# NG2094_IR_Flood.net
KiCad netlist of a schematic drawn in Altium Designer
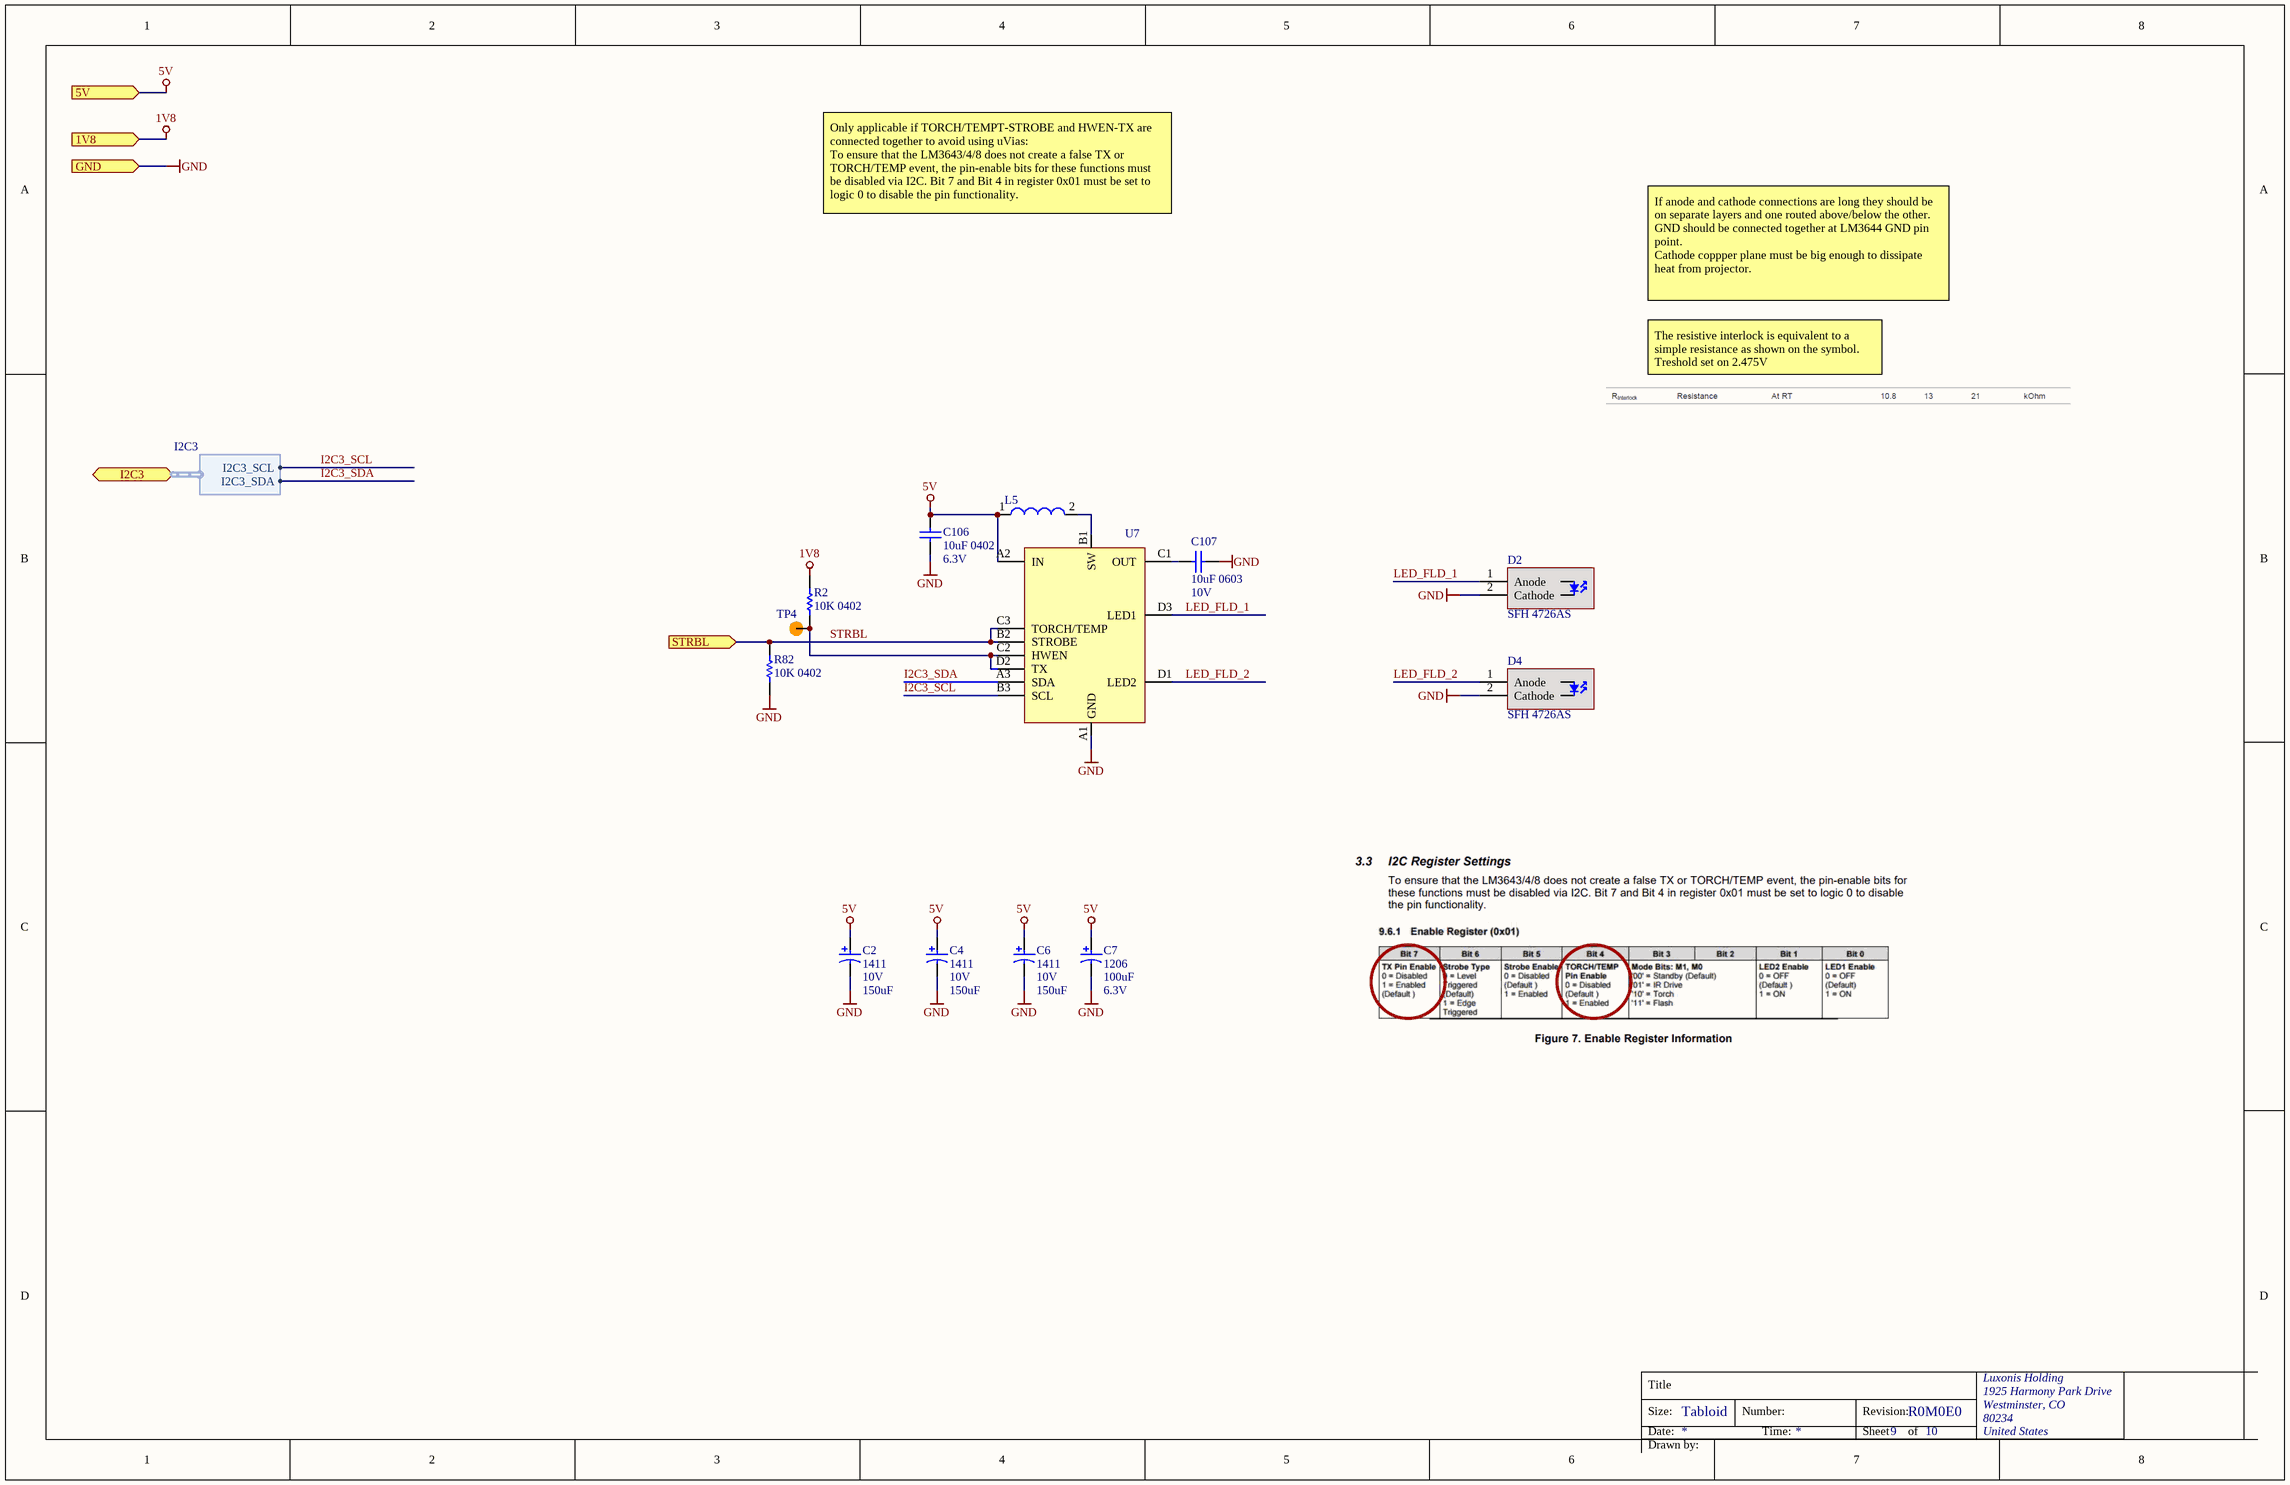
[diagram p0: NG2094_IR_Flood.SchDoc]

(export (version "E")
  (design (tool "Eeschema 10.0.6"))
  (components
    (comp (ref "C2")
      (value "150uF 1206 10V tantal")
      (footprint "RESTL1210(3225)_N")
      (fields
        (field (name "SIZE CODE") "1411")
        (field (name "RATED DC VOLTAGE (URDC)") "10V")
        (field (name "CAPACITANCE") "150uF")
      )
      (libsource (lib "NG2094") (part "TLJB157M010R0500"))
    )
    (comp (ref "C4")
      (value "150uF 1206 10V tantal")
      (footprint "RESTL1210(3225)_N")
      (fields
        (field (name "SIZE CODE") "1411")
        (field (name "RATED DC VOLTAGE (URDC)") "10V")
        (field (name "CAPACITANCE") "150uF")
      )
      (libsource (lib "NG2094") (part "TLJB157M010R0500"))
    )
    (comp (ref "C6")
      (value "150uF 1206 10V tantal")
      (footprint "RESTL1210(3225)_N")
      (fields
        (field (name "SIZE CODE") "1411")
        (field (name "RATED DC VOLTAGE (URDC)") "10V")
        (field (name "CAPACITANCE") "150uF")
      )
      (libsource (lib "NG2094") (part "TLJB157M010R0500"))
    )
    (comp (ref "C7")
      (value "100uF 1206 6V3 tantal")
      (footprint "RESTL1206(3216)_L")
      (fields
        (field (name "SIZE CODE") "1206")
        (field (name "CAPACITANCE") "100uF")
        (field (name "RATED DC VOLTAGE (URDC)") "6.3V")
      )
      (libsource (lib "NG2094") (part "TLJA107M006R0500"))
    )
    (comp (ref "C106")
      (value "10uF 0402")
      (footprint "CAP_Altium_Vault_Generic:CAPC0402(1005)70_L")
      (description "CAP CER 10UF 6.3V X5R 0402 20%")
      (fields (field (name "TOLERANCE") "20%") (field (name "VOLTAGE RATING") "6.3V"))
      (libsource (lib "LuxonisMaster") (part "GRM155R60J106ME15D"))
    )
    (comp (ref "C107")
      (value "10uF 0603")
      (footprint "CAP_Altium_Vault_Generic:CAPC0603(1608)100_L")
      (description "CAP CER 10UF 10V X5R 0603 20%")
      (fields (field (name "TOLERANCE") "20%") (field (name "VOLTAGE RATING") "10V"))
      (libsource (lib "LuxonisMaster") (part "GRM188R61A106ME69D"))
    )
    (comp (ref "D2")
      (value "SFH 4726AS")
      (footprint "SFH 4726AS")
      (description "OSLON Black Series (940 nm) - 150°")
      (libsource (lib "NG2094") (part "SFH 4726AS"))
    )
    (comp (ref "D4")
      (value "SFH 4726AS")
      (footprint "SFH 4726AS")
      (description "OSLON Black Series (940 nm) - 150°")
      (libsource (lib "NG2094") (part "SFH 4726AS"))
    )
    (comp (ref "L5")
      (value "1uH, 3.2A, 20%")
      (footprint "LuxonisMaster:DFE252012P-1R0M=P2")
      (description "FIXED IND 1UH 3.2A 42 MOHM SMD")
      (fields (field (name "MANUFACTURER") "Murata") (field (name "TOLERANCE") "20%"))
      (libsource (lib "LuxonisMaster") (part "DFE252012P-1R0M=P2"))
    )
    (comp (ref "R2")
      (value "10K 0402")
      (footprint "RES_Altium_Vault_Generic:RESC0402(1005)_L")
      (fields (field (name "TOLERANCE") "1%"))
      (libsource (lib "LuxonisMaster") (part "RC0402FR-1310KL"))
    )
    (comp (ref "R82")
      (value "10K 0402")
      (footprint "RES_Altium_Vault_Generic:RESC0402(1005)_L")
      (fields (field (name "TOLERANCE") "1%"))
      (libsource (lib "LuxonisMaster") (part "RC0402FR-1310KL"))
    )
    (comp (ref "TP4")
      (value "TP100_200_NS")
      (footprint "LuxonisMaster:TP100_200_NS")
      (libsource (lib "LuxonisMaster") (part "TEST_POINT"))
    )
    (comp (ref "U7")
      (value "LM3644YFFR")
      (footprint "LM3644YFFR")
      (description "LED Driver, 2-Segment, PBGA12")
      (libsource (lib "NG2094") (part "LM3644"))
    )
  )
  (nets
    (net (code "2") (name "/I2C3_SCL") (class "Default")
      (node (ref "U7") (pin "B3") (pinfunction "SCL_B3") (pintype "passive"))
    )
    (net (code "3") (name "/I2C3_SDA") (class "Default")
      (node (ref "U7") (pin "A3") (pinfunction "SDA_A3") (pintype "passive"))
    )
    (net (code "4") (name "/LED_FLD_1") (class "Default")
      (node (ref "D2") (pin "1") (pinfunction "Anode_1") (pintype "passive"))
      (node (ref "U7") (pin "D3") (pinfunction "LED1_D3") (pintype "passive"))
    )
    (net (code "5") (name "/LED_FLD_2") (class "Default")
      (node (ref "D4") (pin "1") (pinfunction "Anode_1") (pintype "passive"))
      (node (ref "U7") (pin "D1") (pinfunction "LED2_D1") (pintype "passive"))
    )
    (net (code "6") (name "/STRBL") (class "Default")
      (node (ref "R82") (pin "2") (pinfunction "2_2") (pintype "passive"))
      (node (ref "U7") (pin "B2") (pinfunction "STROBE_B2") (pintype "passive"))
      (node (ref "U7") (pin "C3") (pinfunction "TORCH/TEMP_C3") (pintype "passive"))
    )
    (net (code "8") (name "1V8") (class "Default")
      (node (ref "R2") (pin "2") (pinfunction "2_2") (pintype "passive"))
    )
    (net (code "9") (name "5V") (class "Default")
      (node (ref "C106") (pin "2") (pinfunction "2_2") (pintype "passive"))
      (node (ref "C2") (pin "1") (pinfunction "1_1") (pintype "passive"))
      (node (ref "C4") (pin "1") (pinfunction "1_1") (pintype "passive"))
      (node (ref "C6") (pin "1") (pinfunction "1_1") (pintype "passive"))
      (node (ref "C7") (pin "1") (pinfunction "1_1") (pintype "passive"))
      (node (ref "L5") (pin "1") (pinfunction "1_1") (pintype "passive"))
      (node (ref "U7") (pin "A2") (pinfunction "IN_A2") (pintype "passive"))
    )
    (net (code "10") (name "GND") (class "Default")
      (node (ref "C106") (pin "1") (pinfunction "1_1") (pintype "passive"))
      (node (ref "C107") (pin "2") (pinfunction "2_2") (pintype "passive"))
      (node (ref "C2") (pin "2") (pinfunction "2_2") (pintype "passive"))
      (node (ref "C4") (pin "2") (pinfunction "2_2") (pintype "passive"))
      (node (ref "C6") (pin "2") (pinfunction "2_2") (pintype "passive"))
      (node (ref "C7") (pin "2") (pinfunction "2_2") (pintype "passive"))
      (node (ref "D2") (pin "2") (pinfunction "Cathode_2") (pintype "passive"))
      (node (ref "D4") (pin "2") (pinfunction "Cathode_2") (pintype "passive"))
      (node (ref "R82") (pin "1") (pinfunction "1_1") (pintype "passive"))
      (node (ref "U7") (pin "A1") (pinfunction "GND_A1") (pintype "passive"))
    )
    (net (code "11") (name "Net-(U7-HWEN)") (class "Default")
      (node (ref "R2") (pin "1") (pinfunction "1_1") (pintype "passive"))
      (node (ref "TP4") (pin "1") (pintype "passive"))
      (node (ref "U7") (pin "C2") (pinfunction "HWEN_C2") (pintype "passive"))
      (node (ref "U7") (pin "D2") (pinfunction "TX_D2") (pintype "passive"))
    )
    (net (code "12") (name "Net-(U7-OUT)") (class "Default")
      (node (ref "C107") (pin "1") (pinfunction "1_1") (pintype "passive"))
      (node (ref "U7") (pin "C1") (pinfunction "OUT_C1") (pintype "passive"))
    )
    (net (code "13") (name "Net-(U7-SW)") (class "Default")
      (node (ref "L5") (pin "2") (pinfunction "2_2") (pintype "passive"))
      (node (ref "U7") (pin "B1") (pinfunction "SW_B1") (pintype "passive"))
    )
  )
)
